# EasyEDA_open-AutopilotPanel.net
KiCad netlist of a schematic drawn in EasyEDA
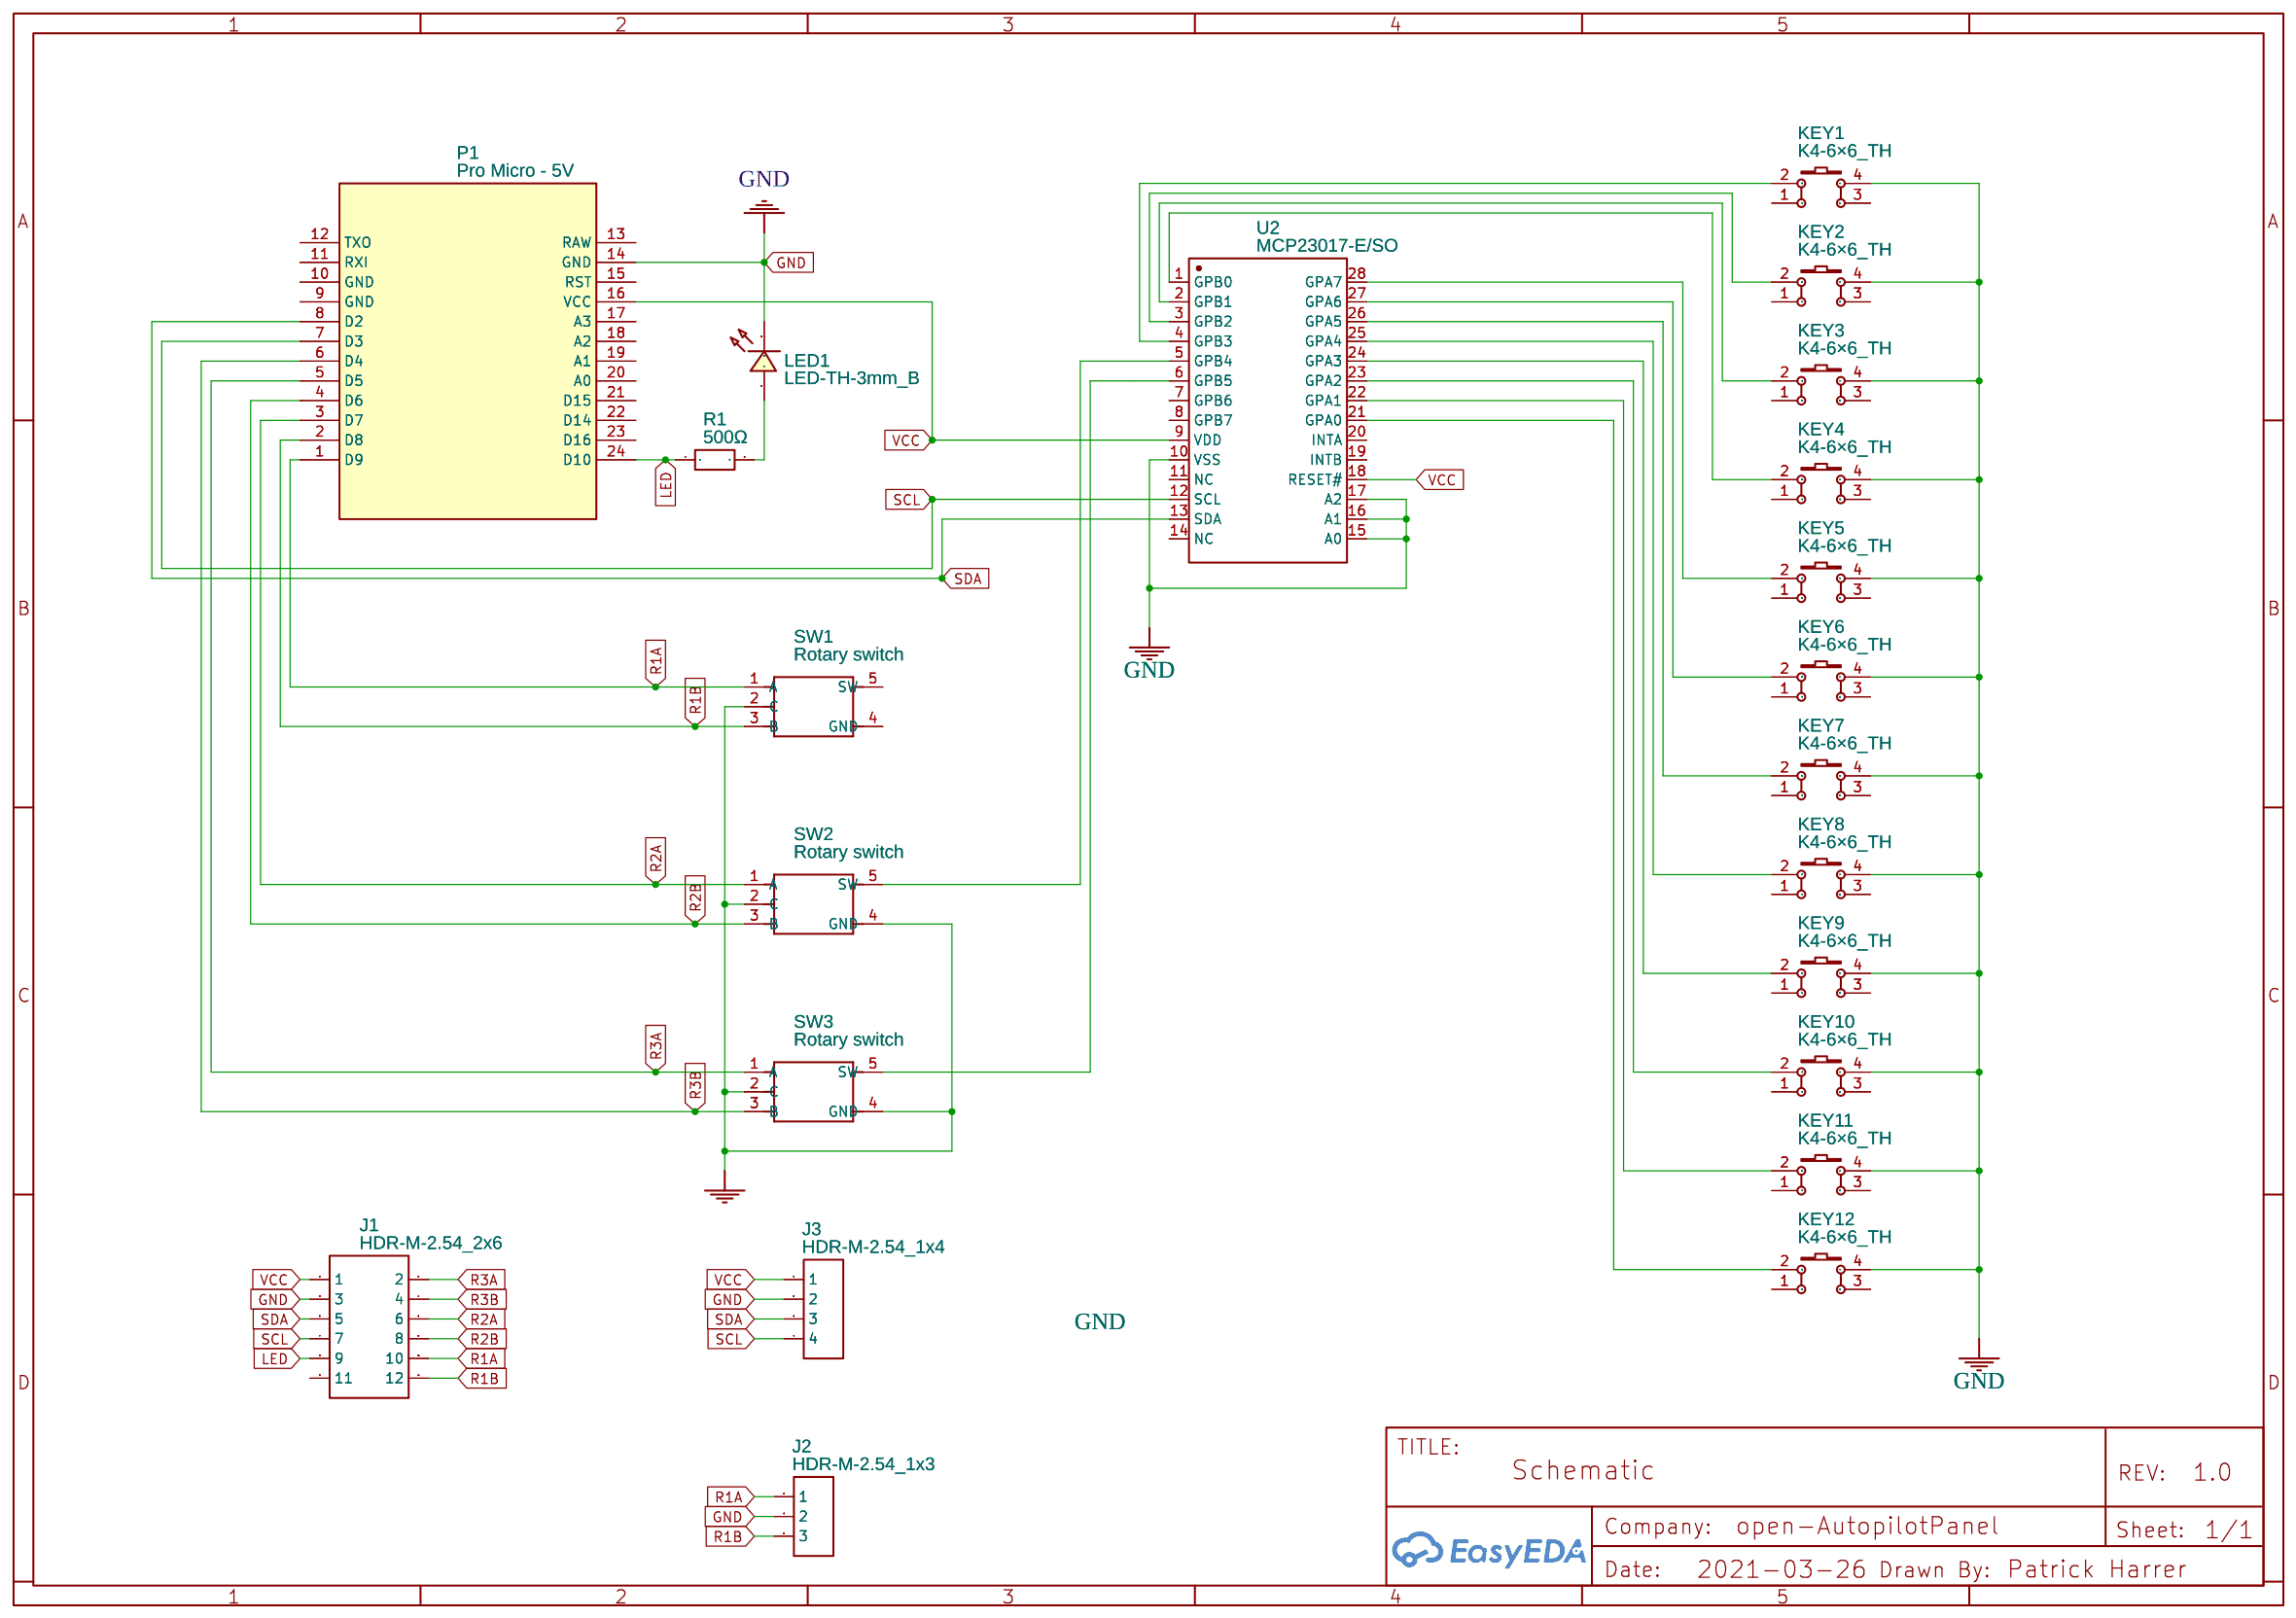
[diagram p0: schematic sheet]

(export (version "E")
  (design (tool "Eeschema 10.0.6"))
  (components
    (comp (ref "J1")
      (value "HDR-M-2.54_2x6")
      (fields (field (name "BOM_Supplier Part") "C124388"))
      (libsource (lib "") (part "HDR-M-2.54_2x6"))
    )
    (comp (ref "J2")
      (value "HDR-M-2.54_1x3")
      (fields (field (name "BOM_Supplier Part") "C180248"))
      (libsource (lib "") (part "HDR-M-2.54_1x3"))
    )
    (comp (ref "J3")
      (value "HDR-M-2.54_1x4")
      (fields (field (name "BOM_Supplier Part") "C124378"))
      (libsource (lib "") (part "HDR-M-2.54_1x4"))
    )
    (comp (ref "KEY1")
      (value "K4-6×6_TH")
      (fields
        (field (name "BOM_Manufacturer Part") "K2-1102DP-E4SW-04")
        (field (name "BOM_Supplier Part") "C136684")
      )
      (libsource (lib "") (part "K4-6×6_TH"))
    )
    (comp (ref "KEY2")
      (value "K4-6×6_TH")
      (fields
        (field (name "BOM_Manufacturer Part") "K2-1102DP-E4SW-04")
        (field (name "BOM_Supplier Part") "C136684")
      )
      (libsource (lib "") (part "K4-6×6_TH"))
    )
    (comp (ref "KEY3")
      (value "K4-6×6_TH")
      (fields
        (field (name "BOM_Manufacturer Part") "K2-1102DP-E4SW-04")
        (field (name "BOM_Supplier Part") "C136684")
      )
      (libsource (lib "") (part "K4-6×6_TH"))
    )
    (comp (ref "KEY4")
      (value "K4-6×6_TH")
      (fields
        (field (name "BOM_Manufacturer Part") "K2-1102DP-E4SW-04")
        (field (name "BOM_Supplier Part") "C136684")
      )
      (libsource (lib "") (part "K4-6×6_TH"))
    )
    (comp (ref "KEY5")
      (value "K4-6×6_TH")
      (fields
        (field (name "BOM_Manufacturer Part") "K2-1102DP-E4SW-04")
        (field (name "BOM_Supplier Part") "C136684")
      )
      (libsource (lib "") (part "K4-6×6_TH"))
    )
    (comp (ref "KEY6")
      (value "K4-6×6_TH")
      (fields
        (field (name "BOM_Manufacturer Part") "K2-1102DP-E4SW-04")
        (field (name "BOM_Supplier Part") "C136684")
      )
      (libsource (lib "") (part "K4-6×6_TH"))
    )
    (comp (ref "KEY7")
      (value "K4-6×6_TH")
      (fields
        (field (name "BOM_Manufacturer Part") "K2-1102DP-E4SW-04")
        (field (name "BOM_Supplier Part") "C136684")
      )
      (libsource (lib "") (part "K4-6×6_TH"))
    )
    (comp (ref "KEY8")
      (value "K4-6×6_TH")
      (fields
        (field (name "BOM_Manufacturer Part") "K2-1102DP-E4SW-04")
        (field (name "BOM_Supplier Part") "C136684")
      )
      (libsource (lib "") (part "K4-6×6_TH"))
    )
    (comp (ref "KEY9")
      (value "K4-6×6_TH")
      (fields
        (field (name "BOM_Manufacturer Part") "K2-1102DP-E4SW-04")
        (field (name "BOM_Supplier Part") "C136684")
      )
      (libsource (lib "") (part "K4-6×6_TH"))
    )
    (comp (ref "KEY10")
      (value "K4-6×6_TH")
      (fields
        (field (name "BOM_Manufacturer Part") "K2-1102DP-E4SW-04")
        (field (name "BOM_Supplier Part") "C136684")
      )
      (libsource (lib "") (part "K4-6×6_TH"))
    )
    (comp (ref "KEY11")
      (value "K4-6×6_TH")
      (fields
        (field (name "BOM_Manufacturer Part") "K2-1102DP-E4SW-04")
        (field (name "BOM_Supplier Part") "C136684")
      )
      (libsource (lib "") (part "K4-6×6_TH"))
    )
    (comp (ref "KEY12")
      (value "K4-6×6_TH")
      (fields
        (field (name "BOM_Manufacturer Part") "K2-1102DP-E4SW-04")
        (field (name "BOM_Supplier Part") "C136684")
      )
      (libsource (lib "") (part "K4-6×6_TH"))
    )
    (comp (ref "LED1")
      (value "LED-TH-3mm_B")
      (fields
        (field (name "BOM_Manufacturer Part") "204-10SUBC/S400-A4")
        (field (name "BOM_Supplier Part") "C86881")
      )
      (libsource (lib "") (part "LED-TH-3mm_B"))
    )
    (comp (ref "P1") (value "Pro Micro - 5V") (libsource (lib "") (part "Pro Micro - 5V")))
    (comp (ref "R1") (value "500Ω") (libsource (lib "") (part "R_AXIAL-0.4_EU")))
    (comp (ref "SW1") (value "Rotary switch") (libsource (lib "") (part "Rotary switch")))
    (comp (ref "SW2") (value "Rotary switch") (libsource (lib "") (part "Rotary switch")))
    (comp (ref "SW3") (value "Rotary switch") (libsource (lib "") (part "Rotary switch")))
    (comp (ref "U2")
      (value "MCP23017-E/SO")
      (fields (field (name "BOM_Supplier Part") "C47023"))
      (libsource (lib "") (part "MCP23017-E/SO"))
    )
  )
  (nets
    (net (code "1") (name "GND") (class "Default")
      (node (ref "J1") (pin "3") (pinfunction "3_3") (pintype "unspecified"))
      (node (ref "J2") (pin "2") (pinfunction "2_2") (pintype "input"))
      (node (ref "J3") (pin "2") (pinfunction "2_2") (pintype "unspecified"))
      (node (ref "KEY1") (pin "4") (pinfunction "4_4") (pintype "unspecified"))
      (node (ref "KEY10") (pin "4") (pinfunction "4_4") (pintype "unspecified"))
      (node (ref "KEY11") (pin "4") (pinfunction "4_4") (pintype "unspecified"))
      (node (ref "KEY12") (pin "4") (pinfunction "4_4") (pintype "unspecified"))
      (node (ref "KEY2") (pin "4") (pinfunction "4_4") (pintype "unspecified"))
      (node (ref "KEY3") (pin "4") (pinfunction "4_4") (pintype "unspecified"))
      (node (ref "KEY4") (pin "4") (pinfunction "4_4") (pintype "unspecified"))
      (node (ref "KEY5") (pin "4") (pinfunction "4_4") (pintype "unspecified"))
      (node (ref "KEY6") (pin "4") (pinfunction "4_4") (pintype "unspecified"))
      (node (ref "KEY7") (pin "4") (pinfunction "4_4") (pintype "unspecified"))
      (node (ref "KEY8") (pin "4") (pinfunction "4_4") (pintype "unspecified"))
      (node (ref "KEY9") (pin "4") (pinfunction "4_4") (pintype "unspecified"))
      (node (ref "LED1") (pin "2") (pinfunction "2_2") (pintype "unspecified"))
      (node (ref "P1") (pin "14") (pinfunction "GND_14") (pintype "unspecified"))
      (node (ref "SW1") (pin "2") (pinfunction "C_2") (pintype "unspecified"))
      (node (ref "SW2") (pin "2") (pinfunction "C_2") (pintype "unspecified"))
      (node (ref "SW2") (pin "4") (pinfunction "GND_4") (pintype "unspecified"))
      (node (ref "SW3") (pin "2") (pinfunction "C_2") (pintype "unspecified"))
      (node (ref "SW3") (pin "4") (pinfunction "GND_4") (pintype "unspecified"))
      (node (ref "U2") (pin "10") (pinfunction "VSS_10") (pintype "unspecified"))
      (node (ref "U2") (pin "15") (pinfunction "A0_15") (pintype "unspecified"))
      (node (ref "U2") (pin "16") (pinfunction "A1_16") (pintype "unspecified"))
      (node (ref "U2") (pin "17") (pinfunction "A2_17") (pintype "unspecified"))
    )
    (net (code "2") (name "LED") (class "Default")
      (node (ref "J1") (pin "9") (pinfunction "9_9") (pintype "unspecified"))
      (node (ref "P1") (pin "24") (pinfunction "D10_24") (pintype "unspecified"))
      (node (ref "R1") (pin "1") (pinfunction "1_1") (pintype "unspecified"))
    )
    (net (code "3") (name "Net-(LED1-Pad1)") (class "Default")
      (node (ref "LED1") (pin "1") (pinfunction "1_1") (pintype "unspecified"))
      (node (ref "R1") (pin "2") (pinfunction "2_2") (pintype "unspecified"))
    )
    (net (code "4") (name "Net-(SW2-SW)") (class "Default")
      (node (ref "SW2") (pin "5") (pinfunction "SW_5") (pintype "unspecified"))
      (node (ref "U2") (pin "5") (pinfunction "GPB4_5") (pintype "unspecified"))
    )
    (net (code "5") (name "Net-(SW3-SW)") (class "Default")
      (node (ref "SW3") (pin "5") (pinfunction "SW_5") (pintype "unspecified"))
      (node (ref "U2") (pin "6") (pinfunction "GPB5_6") (pintype "unspecified"))
    )
    (net (code "6") (name "Net-(U2-GPA0)") (class "Default")
      (node (ref "KEY12") (pin "2") (pinfunction "2_2") (pintype "unspecified"))
      (node (ref "U2") (pin "21") (pinfunction "GPA0_21") (pintype "unspecified"))
    )
    (net (code "7") (name "Net-(U2-GPA1)") (class "Default")
      (node (ref "KEY11") (pin "2") (pinfunction "2_2") (pintype "unspecified"))
      (node (ref "U2") (pin "22") (pinfunction "GPA1_22") (pintype "unspecified"))
    )
    (net (code "8") (name "Net-(U2-GPA2)") (class "Default")
      (node (ref "KEY10") (pin "2") (pinfunction "2_2") (pintype "unspecified"))
      (node (ref "U2") (pin "23") (pinfunction "GPA2_23") (pintype "unspecified"))
    )
    (net (code "9") (name "Net-(U2-GPA3)") (class "Default")
      (node (ref "KEY9") (pin "2") (pinfunction "2_2") (pintype "unspecified"))
      (node (ref "U2") (pin "24") (pinfunction "GPA3_24") (pintype "unspecified"))
    )
    (net (code "10") (name "Net-(U2-GPA4)") (class "Default")
      (node (ref "KEY8") (pin "2") (pinfunction "2_2") (pintype "unspecified"))
      (node (ref "U2") (pin "25") (pinfunction "GPA4_25") (pintype "unspecified"))
    )
    (net (code "11") (name "Net-(U2-GPA5)") (class "Default")
      (node (ref "KEY7") (pin "2") (pinfunction "2_2") (pintype "unspecified"))
      (node (ref "U2") (pin "26") (pinfunction "GPA5_26") (pintype "unspecified"))
    )
    (net (code "12") (name "Net-(U2-GPA6)") (class "Default")
      (node (ref "KEY6") (pin "2") (pinfunction "2_2") (pintype "unspecified"))
      (node (ref "U2") (pin "27") (pinfunction "GPA6_27") (pintype "unspecified"))
    )
    (net (code "13") (name "Net-(U2-GPA7)") (class "Default")
      (node (ref "KEY5") (pin "2") (pinfunction "2_2") (pintype "unspecified"))
      (node (ref "U2") (pin "28") (pinfunction "GPA7_28") (pintype "unspecified"))
    )
    (net (code "14") (name "Net-(U2-GPB0)") (class "Default")
      (node (ref "KEY4") (pin "2") (pinfunction "2_2") (pintype "unspecified"))
      (node (ref "U2") (pin "1") (pinfunction "GPB0_1") (pintype "unspecified"))
    )
    (net (code "15") (name "Net-(U2-GPB1)") (class "Default")
      (node (ref "KEY3") (pin "2") (pinfunction "2_2") (pintype "unspecified"))
      (node (ref "U2") (pin "2") (pinfunction "GPB1_2") (pintype "unspecified"))
    )
    (net (code "16") (name "Net-(U2-GPB2)") (class "Default")
      (node (ref "KEY2") (pin "2") (pinfunction "2_2") (pintype "unspecified"))
      (node (ref "U2") (pin "3") (pinfunction "GPB2_3") (pintype "unspecified"))
    )
    (net (code "17") (name "Net-(U2-GPB3)") (class "Default")
      (node (ref "KEY1") (pin "2") (pinfunction "2_2") (pintype "unspecified"))
      (node (ref "U2") (pin "4") (pinfunction "GPB3_4") (pintype "unspecified"))
    )
    (net (code "18") (name "R1A") (class "Default")
      (node (ref "J1") (pin "10") (pinfunction "10_10") (pintype "unspecified"))
      (node (ref "J2") (pin "1") (pinfunction "1_1") (pintype "input"))
      (node (ref "P1") (pin "1") (pinfunction "D9_1") (pintype "unspecified"))
      (node (ref "SW1") (pin "1") (pinfunction "A_1") (pintype "unspecified"))
    )
    (net (code "19") (name "R1B") (class "Default")
      (node (ref "J1") (pin "12") (pinfunction "12_12") (pintype "unspecified"))
      (node (ref "J2") (pin "3") (pinfunction "3_3") (pintype "input"))
      (node (ref "P1") (pin "2") (pinfunction "D8_2") (pintype "unspecified"))
      (node (ref "SW1") (pin "3") (pinfunction "B_3") (pintype "unspecified"))
    )
    (net (code "20") (name "R2A") (class "Default")
      (node (ref "J1") (pin "6") (pinfunction "6_6") (pintype "unspecified"))
      (node (ref "P1") (pin "3") (pinfunction "D7_3") (pintype "unspecified"))
      (node (ref "SW2") (pin "1") (pinfunction "A_1") (pintype "unspecified"))
    )
    (net (code "21") (name "R2B") (class "Default")
      (node (ref "J1") (pin "8") (pinfunction "8_8") (pintype "unspecified"))
      (node (ref "P1") (pin "4") (pinfunction "D6_4") (pintype "unspecified"))
      (node (ref "SW2") (pin "3") (pinfunction "B_3") (pintype "unspecified"))
    )
    (net (code "22") (name "R3A") (class "Default")
      (node (ref "J1") (pin "2") (pinfunction "2_2") (pintype "unspecified"))
      (node (ref "P1") (pin "5") (pinfunction "D5_5") (pintype "unspecified"))
      (node (ref "SW3") (pin "1") (pinfunction "A_1") (pintype "unspecified"))
    )
    (net (code "23") (name "R3B") (class "Default")
      (node (ref "J1") (pin "4") (pinfunction "4_4") (pintype "unspecified"))
      (node (ref "P1") (pin "6") (pinfunction "D4_6") (pintype "unspecified"))
      (node (ref "SW3") (pin "3") (pinfunction "B_3") (pintype "unspecified"))
    )
    (net (code "24") (name "SCL") (class "Default")
      (node (ref "J1") (pin "7") (pinfunction "7_7") (pintype "unspecified"))
      (node (ref "J3") (pin "4") (pinfunction "4_4") (pintype "unspecified"))
      (node (ref "P1") (pin "7") (pinfunction "D3_7") (pintype "unspecified"))
      (node (ref "U2") (pin "12") (pinfunction "SCL_12") (pintype "unspecified"))
    )
    (net (code "25") (name "SDA") (class "Default")
      (node (ref "J1") (pin "5") (pinfunction "5_5") (pintype "unspecified"))
      (node (ref "J3") (pin "3") (pinfunction "3_3") (pintype "unspecified"))
      (node (ref "P1") (pin "8") (pinfunction "D2_8") (pintype "unspecified"))
      (node (ref "U2") (pin "13") (pinfunction "SDA_13") (pintype "unspecified"))
    )
    (net (code "26") (name "VCC") (class "Default")
      (node (ref "J1") (pin "1") (pinfunction "1_1") (pintype "unspecified"))
      (node (ref "J3") (pin "1") (pinfunction "1_1") (pintype "unspecified"))
      (node (ref "P1") (pin "16") (pinfunction "VCC_16") (pintype "unspecified"))
      (node (ref "U2") (pin "18") (pinfunction "RESET#_18") (pintype "unspecified"))
      (node (ref "U2") (pin "9") (pinfunction "VDD_9") (pintype "unspecified"))
    )
    (net (code "27") (name "unconnected-(J1-Pad11)") (class "Default")
      (node (ref "J1") (pin "11") (pinfunction "11_11") (pintype "unspecified"))
    )
    (net (code "28") (name "unconnected-(KEY1-Pad1)") (class "Default")
      (node (ref "KEY1") (pin "1") (pinfunction "1_1") (pintype "unspecified"))
    )
    (net (code "29") (name "unconnected-(KEY1-Pad3)") (class "Default")
      (node (ref "KEY1") (pin "3") (pinfunction "3_3") (pintype "unspecified"))
    )
    (net (code "30") (name "unconnected-(KEY2-Pad1)") (class "Default")
      (node (ref "KEY2") (pin "1") (pinfunction "1_1") (pintype "unspecified"))
    )
    (net (code "31") (name "unconnected-(KEY2-Pad3)") (class "Default")
      (node (ref "KEY2") (pin "3") (pinfunction "3_3") (pintype "unspecified"))
    )
    (net (code "32") (name "unconnected-(KEY3-Pad1)") (class "Default")
      (node (ref "KEY3") (pin "1") (pinfunction "1_1") (pintype "unspecified"))
    )
    (net (code "33") (name "unconnected-(KEY3-Pad3)") (class "Default")
      (node (ref "KEY3") (pin "3") (pinfunction "3_3") (pintype "unspecified"))
    )
    (net (code "34") (name "unconnected-(KEY4-Pad1)") (class "Default")
      (node (ref "KEY4") (pin "1") (pinfunction "1_1") (pintype "unspecified"))
    )
    (net (code "35") (name "unconnected-(KEY4-Pad3)") (class "Default")
      (node (ref "KEY4") (pin "3") (pinfunction "3_3") (pintype "unspecified"))
    )
    (net (code "36") (name "unconnected-(KEY5-Pad1)") (class "Default")
      (node (ref "KEY5") (pin "1") (pinfunction "1_1") (pintype "unspecified"))
    )
    (net (code "37") (name "unconnected-(KEY5-Pad3)") (class "Default")
      (node (ref "KEY5") (pin "3") (pinfunction "3_3") (pintype "unspecified"))
    )
    (net (code "38") (name "unconnected-(KEY6-Pad1)") (class "Default")
      (node (ref "KEY6") (pin "1") (pinfunction "1_1") (pintype "unspecified"))
    )
    (net (code "39") (name "unconnected-(KEY6-Pad3)") (class "Default")
      (node (ref "KEY6") (pin "3") (pinfunction "3_3") (pintype "unspecified"))
    )
    (net (code "40") (name "unconnected-(KEY7-Pad1)") (class "Default")
      (node (ref "KEY7") (pin "1") (pinfunction "1_1") (pintype "unspecified"))
    )
    (net (code "41") (name "unconnected-(KEY7-Pad3)") (class "Default")
      (node (ref "KEY7") (pin "3") (pinfunction "3_3") (pintype "unspecified"))
    )
    (net (code "42") (name "unconnected-(KEY8-Pad1)") (class "Default")
      (node (ref "KEY8") (pin "1") (pinfunction "1_1") (pintype "unspecified"))
    )
    (net (code "43") (name "unconnected-(KEY8-Pad3)") (class "Default")
      (node (ref "KEY8") (pin "3") (pinfunction "3_3") (pintype "unspecified"))
    )
    (net (code "44") (name "unconnected-(KEY9-Pad1)") (class "Default")
      (node (ref "KEY9") (pin "1") (pinfunction "1_1") (pintype "unspecified"))
    )
    (net (code "45") (name "unconnected-(KEY9-Pad3)") (class "Default")
      (node (ref "KEY9") (pin "3") (pinfunction "3_3") (pintype "unspecified"))
    )
    (net (code "46") (name "unconnected-(KEY10-Pad1)") (class "Default")
      (node (ref "KEY10") (pin "1") (pinfunction "1_1") (pintype "unspecified"))
    )
    (net (code "47") (name "unconnected-(KEY10-Pad3)") (class "Default")
      (node (ref "KEY10") (pin "3") (pinfunction "3_3") (pintype "unspecified"))
    )
    (net (code "48") (name "unconnected-(KEY11-Pad1)") (class "Default")
      (node (ref "KEY11") (pin "1") (pinfunction "1_1") (pintype "unspecified"))
    )
    (net (code "49") (name "unconnected-(KEY11-Pad3)") (class "Default")
      (node (ref "KEY11") (pin "3") (pinfunction "3_3") (pintype "unspecified"))
    )
    (net (code "50") (name "unconnected-(KEY12-Pad1)") (class "Default")
      (node (ref "KEY12") (pin "1") (pinfunction "1_1") (pintype "unspecified"))
    )
    (net (code "51") (name "unconnected-(KEY12-Pad3)") (class "Default")
      (node (ref "KEY12") (pin "3") (pinfunction "3_3") (pintype "unspecified"))
    )
    (net (code "52") (name "unconnected-(P1-A0-Pad20)") (class "Default")
      (node (ref "P1") (pin "20") (pinfunction "A0_20") (pintype "unspecified"))
    )
    (net (code "53") (name "unconnected-(P1-A1-Pad19)") (class "Default")
      (node (ref "P1") (pin "19") (pinfunction "A1_19") (pintype "unspecified"))
    )
    (net (code "54") (name "unconnected-(P1-A2-Pad18)") (class "Default")
      (node (ref "P1") (pin "18") (pinfunction "A2_18") (pintype "unspecified"))
    )
    (net (code "55") (name "unconnected-(P1-A3-Pad17)") (class "Default")
      (node (ref "P1") (pin "17") (pinfunction "A3_17") (pintype "unspecified"))
    )
    (net (code "56") (name "unconnected-(P1-D14-Pad22)") (class "Default")
      (node (ref "P1") (pin "22") (pinfunction "D14_22") (pintype "unspecified"))
    )
    (net (code "57") (name "unconnected-(P1-D15-Pad21)") (class "Default")
      (node (ref "P1") (pin "21") (pinfunction "D15_21") (pintype "unspecified"))
    )
    (net (code "58") (name "unconnected-(P1-D16-Pad23)") (class "Default")
      (node (ref "P1") (pin "23") (pinfunction "D16_23") (pintype "unspecified"))
    )
    (net (code "59") (name "unconnected-(P1-GND-Pad9)") (class "Default")
      (node (ref "P1") (pin "9") (pinfunction "GND_9") (pintype "unspecified"))
    )
    (net (code "60") (name "unconnected-(P1-GND-Pad10)") (class "Default")
      (node (ref "P1") (pin "10") (pinfunction "GND_10") (pintype "unspecified"))
    )
    (net (code "61") (name "unconnected-(P1-RAW-Pad13)") (class "Default")
      (node (ref "P1") (pin "13") (pinfunction "RAW_13") (pintype "unspecified"))
    )
    (net (code "62") (name "unconnected-(P1-RST-Pad15)") (class "Default")
      (node (ref "P1") (pin "15") (pinfunction "RST_15") (pintype "unspecified"))
    )
    (net (code "63") (name "unconnected-(P1-RXI-Pad11)") (class "Default")
      (node (ref "P1") (pin "11") (pinfunction "RXI_11") (pintype "unspecified"))
    )
    (net (code "64") (name "unconnected-(P1-TXO-Pad12)") (class "Default")
      (node (ref "P1") (pin "12") (pinfunction "TXO_12") (pintype "unspecified"))
    )
    (net (code "65") (name "unconnected-(SW1-GND-Pad4)") (class "Default")
      (node (ref "SW1") (pin "4") (pinfunction "GND_4") (pintype "unspecified"))
    )
    (net (code "66") (name "unconnected-(SW1-SW-Pad5)") (class "Default")
      (node (ref "SW1") (pin "5") (pinfunction "SW_5") (pintype "unspecified"))
    )
    (net (code "67") (name "unconnected-(U2-GPB6-Pad7)") (class "Default")
      (node (ref "U2") (pin "7") (pinfunction "GPB6_7") (pintype "unspecified"))
    )
    (net (code "68") (name "unconnected-(U2-GPB7-Pad8)") (class "Default")
      (node (ref "U2") (pin "8") (pinfunction "GPB7_8") (pintype "unspecified"))
    )
    (net (code "69") (name "unconnected-(U2-INTA-Pad20)") (class "Default")
      (node (ref "U2") (pin "20") (pinfunction "INTA_20") (pintype "unspecified"))
    )
    (net (code "70") (name "unconnected-(U2-INTB-Pad19)") (class "Default")
      (node (ref "U2") (pin "19") (pinfunction "INTB_19") (pintype "unspecified"))
    )
    (net (code "71") (name "unconnected-(U2-NC-Pad11)") (class "Default")
      (node (ref "U2") (pin "11") (pinfunction "NC_11") (pintype "unspecified"))
    )
    (net (code "72") (name "unconnected-(U2-NC-Pad14)") (class "Default")
      (node (ref "U2") (pin "14") (pinfunction "NC_14") (pintype "unspecified"))
    )
  )
)
